# BDxxGC0WEFJ_Lineer_regulator.net
KiCad netlist of a schematic drawn in EAGLE
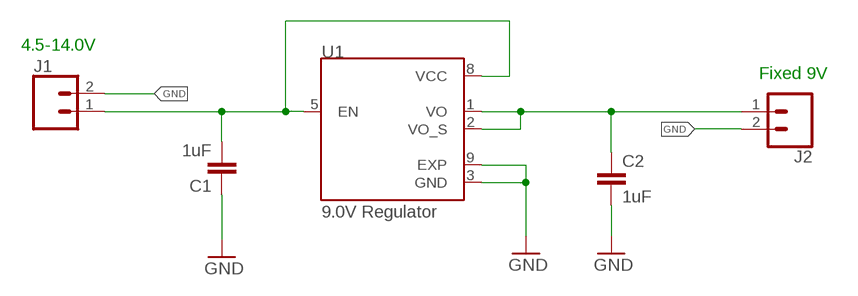
[diagram p0: schematic, sheet 1]

(export (version "E")
  (design (tool "Eeschema 10.0.6"))
  (components
    (comp (ref "C1")
      (value "1uF")
      (footprint "eagle-import:C0603")
      (libsource (lib "eagle-import") (part "C-EUC0603"))
    )
    (comp (ref "C2")
      (value "1uF")
      (footprint "eagle-import:C0603")
      (libsource (lib "eagle-import") (part "C-EUC0603"))
    )
    (comp (ref "J1")
      (value "CONN_02")
      (footprint "eagle-import:1X02")
      (libsource (lib "eagle-import") (part "CONN_02"))
    )
    (comp (ref "J2")
      (value "CONN_02")
      (footprint "eagle-import:1X02")
      (libsource (lib "eagle-import") (part "CONN_02"))
    )
    (comp (ref "U1")
      (value "9.0V Regulator")
      (footprint "eagle-import:SOIC127P600X100-9N")
      (fields (field (name "MF") "Rohm") (field (name "MP") "BD50GC0WEFJ-E2"))
      (libsource (lib "eagle-import") (part "BD50GC0WEFJ-E2"))
    )
  )
  (nets
    (net (code "1") (name "GND") (class "Default")
      (node (ref "C1") (pin "1") (pinfunction "1_1") (pintype "passive"))
      (node (ref "C2") (pin "2") (pinfunction "2_2") (pintype "passive"))
      (node (ref "J1") (pin "2") (pinfunction "2_2") (pintype "passive"))
      (node (ref "J2") (pin "2") (pinfunction "2_2") (pintype "passive"))
      (node (ref "U1") (pin "3") (pinfunction "GND_3") (pintype "power_in"))
      (node (ref "U1") (pin "9") (pinfunction "EXP_9") (pintype "power_in"))
    )
    (net (code "2") (name "Net-(U1-EN)") (class "Default")
      (node (ref "C1") (pin "2") (pinfunction "2_2") (pintype "passive"))
      (node (ref "J1") (pin "1") (pinfunction "1_1") (pintype "passive"))
      (node (ref "U1") (pin "5") (pinfunction "EN_5") (pintype "input"))
      (node (ref "U1") (pin "8") (pinfunction "VCC_8") (pintype "power_in"))
    )
    (net (code "3") (name "Net-(U1-VO)") (class "Default")
      (node (ref "C2") (pin "1") (pinfunction "1_1") (pintype "passive"))
      (node (ref "J2") (pin "1") (pinfunction "1_1") (pintype "passive"))
      (node (ref "U1") (pin "1") (pinfunction "VO_1") (pintype "output"))
      (node (ref "U1") (pin "2") (pinfunction "VO_S_2") (pintype "output"))
    )
  )
)
